# servo-hbridge.net
KiCad netlist of a schematic drawn in Altium Designer
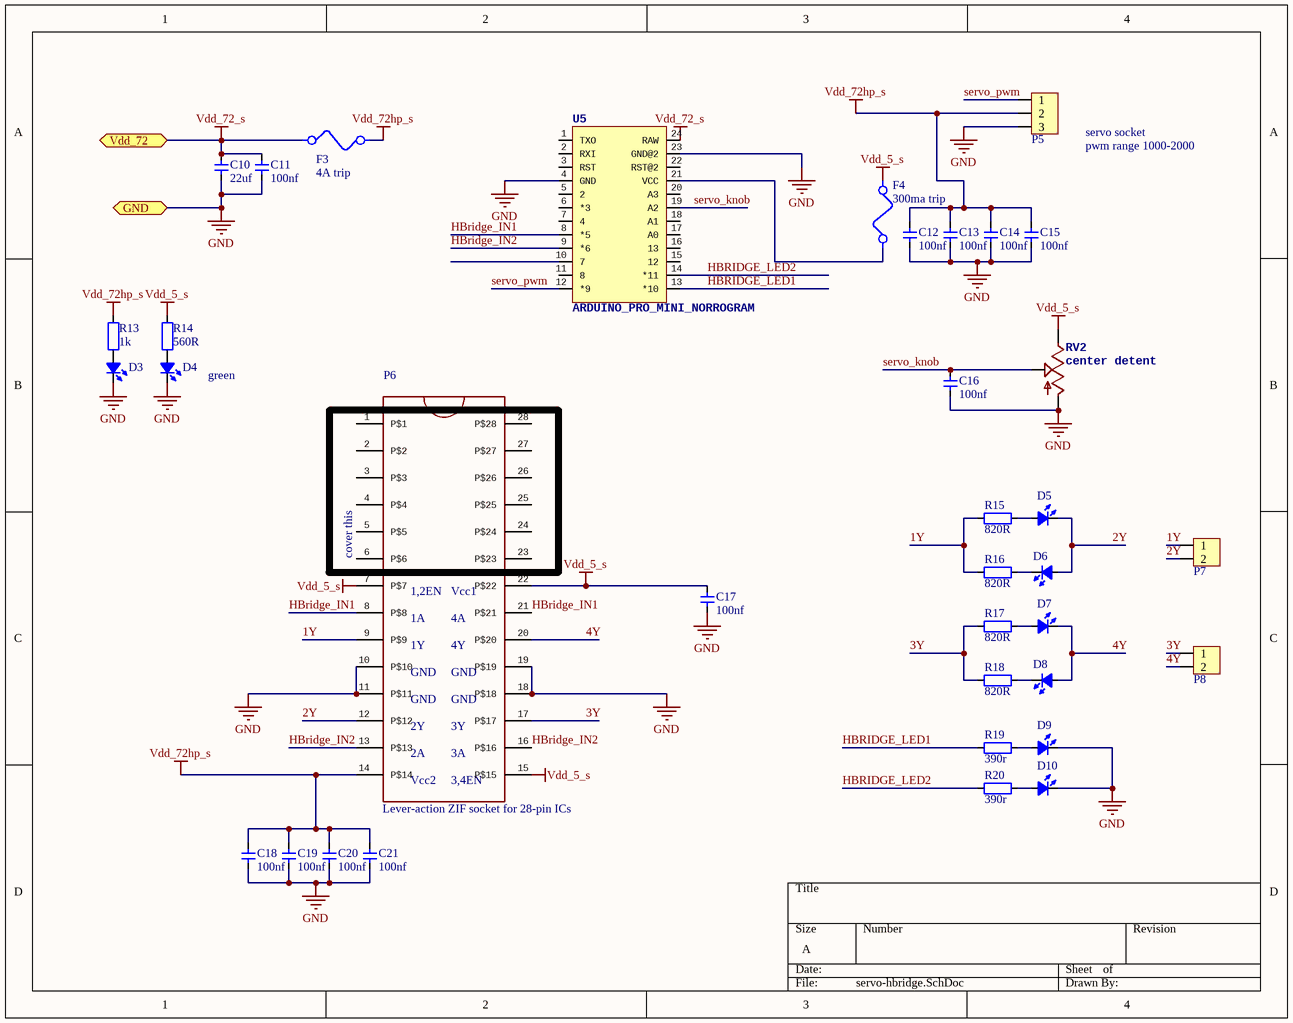
[diagram p0: servo-hbridge.SchDoc]

(export (version "E")
  (design (tool "Eeschema 10.0.6"))
  (components
    (comp (ref "C10")
      (value "22uf")
      (footprint "PCB_PassiveCap:CAP_0805")
      (description "Capacitor")
      (fields (field (name "Comment") "Cap_0805"))
      (libsource (lib "SCH_Passive") (part "Cap_0805"))
    )
    (comp (ref "C11")
      (value "100nf")
      (footprint "PCB_PassiveCap:CAP_0805")
      (description "Capacitor")
      (fields (field (name "Comment") "Cap_0805"))
      (libsource (lib "SCH_Passive") (part "Cap_0805"))
    )
    (comp (ref "C12")
      (value "100nf")
      (footprint "PCB_PassiveCap:CAP_0805")
      (description "Capacitor")
      (fields (field (name "Comment") "Cap_0805"))
      (libsource (lib "SCH_Passive") (part "Cap_0805"))
    )
    (comp (ref "C13")
      (value "100nf")
      (footprint "PCB_PassiveCap:CAP_0805")
      (description "Capacitor")
      (fields (field (name "Comment") "Cap_0805"))
      (libsource (lib "SCH_Passive") (part "Cap_0805"))
    )
    (comp (ref "C14")
      (value "100nf")
      (footprint "PCB_PassiveCap:CAP_0805")
      (description "Capacitor")
      (fields (field (name "Comment") "Cap_0805"))
      (libsource (lib "SCH_Passive") (part "Cap_0805"))
    )
    (comp (ref "C15")
      (value "100nf")
      (footprint "PCB_PassiveCap:CAP_0805")
      (description "Capacitor")
      (fields (field (name "Comment") "Cap_0805"))
      (libsource (lib "SCH_Passive") (part "Cap_0805"))
    )
    (comp (ref "C16")
      (value "100nf")
      (footprint "PCB_PassiveCap:CAP_0805")
      (description "Capacitor")
      (fields (field (name "Comment") "Cap_0805"))
      (libsource (lib "SCH_Passive") (part "Cap_0805"))
    )
    (comp (ref "C17")
      (value "100nf")
      (footprint "PCB_PassiveCap:CAP_0805")
      (description "Capacitor")
      (fields (field (name "Comment") "Cap_0805"))
      (libsource (lib "SCH_Passive") (part "Cap_0805"))
    )
    (comp (ref "C18")
      (value "100nf")
      (footprint "PCB_PassiveCap:CAP_0805")
      (description "Capacitor")
      (fields (field (name "Comment") "Cap_0805"))
      (libsource (lib "SCH_Passive") (part "Cap_0805"))
    )
    (comp (ref "C19")
      (value "100nf")
      (footprint "PCB_PassiveCap:CAP_0805")
      (description "Capacitor")
      (fields (field (name "Comment") "Cap_0805"))
      (libsource (lib "SCH_Passive") (part "Cap_0805"))
    )
    (comp (ref "C20")
      (value "100nf")
      (footprint "PCB_PassiveCap:CAP_0805")
      (description "Capacitor")
      (fields (field (name "Comment") "Cap_0805"))
      (libsource (lib "SCH_Passive") (part "Cap_0805"))
    )
    (comp (ref "C21")
      (value "100nf")
      (footprint "PCB_PassiveCap:CAP_0805")
      (description "Capacitor")
      (fields (field (name "Comment") "Cap_0805"))
      (libsource (lib "SCH_Passive") (part "Cap_0805"))
    )
    (comp (ref "D3")
      (value "LED_0805")
      (footprint "PCB_ActiveLED:LED_0805_RED")
      (description "LED")
      (libsource (lib "SCH_Active") (part "LED_0805"))
    )
    (comp (ref "D4")
      (value "LED_0805")
      (footprint "PCB_ActiveLED:LED_0805_RED")
      (description "LED")
      (libsource (lib "SCH_Active") (part "LED_0805"))
    )
    (comp (ref "D5")
      (value "LED_0805")
      (footprint "PCB_ActiveLED:LED_0805_YELLOW")
      (description "LED")
      (libsource (lib "SCH_Active") (part "LED_0805"))
    )
    (comp (ref "D6")
      (value "LED_0805")
      (footprint "PCB_ActiveLED:LED_0805_YELLOW")
      (description "LED")
      (libsource (lib "SCH_Active") (part "LED_0805"))
    )
    (comp (ref "D7")
      (value "LED_0805")
      (footprint "PCB_ActiveLED:LED_0805_YELLOW")
      (description "LED")
      (libsource (lib "SCH_Active") (part "LED_0805"))
    )
    (comp (ref "D8")
      (value "LED_0805")
      (footprint "PCB_ActiveLED:LED_0805_YELLOW")
      (description "LED")
      (libsource (lib "SCH_Active") (part "LED_0805"))
    )
    (comp (ref "D9")
      (value "LED_0805")
      (footprint "PCB_ActiveLED:LED_0805_YELLOW")
      (description "LED")
      (libsource (lib "SCH_Active") (part "LED_0805"))
    )
    (comp (ref "D10")
      (value "LED_0805")
      (footprint "PCB_ActiveLED:LED_0805_YELLOW")
      (description "LED")
      (libsource (lib "SCH_Active") (part "LED_0805"))
    )
    (comp (ref "F3")
      (value "4A trip")
      (footprint "Multifuse1812")
      (description "RO ZEK MULTI 500MA SMD 1812 MF-MSMF050-2 BOURNS")
      (fields (field (name "MFG") "BOURNS"))
      (libsource (lib "Ultimaker") (part "Multifuse"))
    )
    (comp (ref "F4")
      (value "300ma trip")
      (footprint "Multifuse1812")
      (description "RO ZEK MULTI 500MA SMD 1812 MF-MSMF050-2 BOURNS")
      (fields (field (name "MFG") "BOURNS"))
      (libsource (lib "Ultimaker") (part "Multifuse"))
    )
    (comp (ref "P5")
      (value "HDR1x3_2.54")
      (footprint "PCB_ConnectorHDR:HDR1X3_2.54_180")
      (description "Header")
      (libsource (lib "SCH_ConnectorHDR") (part "HDR1x3_2.54"))
    )
    (comp (ref "P6")
      (value "Lever-action ZIF socket for 28-pin ICs")
      (footprint "DIL28-3-ZIF_SOCKET")
      (libsource (lib "SparkFun-Connectors") (part "ZIFSOCKET-28-3ZIFFSOCKET-28-3"))
    )
    (comp (ref "P7")
      (value "HDR1x2_2.54")
      (footprint "PCB_ConnectorHDR:HDR1X2_2.54_180")
      (description "Header")
      (libsource (lib "SCH_ConnectorHDR") (part "HDR1x2_2.54"))
    )
    (comp (ref "P8")
      (value "HDR1x2_2.54")
      (footprint "PCB_ConnectorHDR:HDR1X2_2.54_180")
      (description "Header")
      (libsource (lib "SCH_ConnectorHDR") (part "HDR1x2_2.54"))
    )
    (comp (ref "R13")
      (value "1k")
      (footprint "PCB_PassiveRes:RES_0805")
      (description "Resistor")
      (fields (field (name "Comment") "Res_0805"))
      (libsource (lib "") (part "Res_0805_1"))
    )
    (comp (ref "R14")
      (value "560R")
      (footprint "PCB_PassiveRes:RES_0805")
      (description "Resistor")
      (fields (field (name "Comment") "Res_0805"))
      (libsource (lib "") (part "Res_0805_1"))
    )
    (comp (ref "R15")
      (value "820R")
      (footprint "PCB_PassiveRes:RES_0805")
      (description "Resistor")
      (fields (field (name "Comment") "Res_0805"))
      (libsource (lib "SCH_Passive") (part "Res_0805"))
    )
    (comp (ref "R16")
      (value "820R")
      (footprint "PCB_PassiveRes:RES_0805")
      (description "Resistor")
      (fields (field (name "Comment") "Res_0805"))
      (libsource (lib "SCH_Passive") (part "Res_0805"))
    )
    (comp (ref "R17")
      (value "820R")
      (footprint "PCB_PassiveRes:RES_0805")
      (description "Resistor")
      (fields (field (name "Comment") "Res_0805"))
      (libsource (lib "SCH_Passive") (part "Res_0805"))
    )
    (comp (ref "R18")
      (value "820R")
      (footprint "PCB_PassiveRes:RES_0805")
      (description "Resistor")
      (fields (field (name "Comment") "Res_0805"))
      (libsource (lib "SCH_Passive") (part "Res_0805"))
    )
    (comp (ref "R19")
      (value "390r")
      (footprint "PCB_PassiveRes:RES_0805")
      (description "Resistor")
      (fields (field (name "Comment") "Res_0805"))
      (libsource (lib "SCH_Passive") (part "Res_0805"))
    )
    (comp (ref "R20")
      (value "390r")
      (footprint "PCB_PassiveRes:RES_0805")
      (description "Resistor")
      (fields (field (name "Comment") "Res_0805"))
      (libsource (lib "SCH_Passive") (part "Res_0805"))
    )
    (comp (ref "RV2")
      (value "center detent")
      (footprint "Bourns-slimline-axialbracket")
      (libsource (lib "SparkFun-Electromechanical") (part "POTALPS-KIT"))
    )
    (comp (ref "U5")
      (value "ARDUINO_PRO_MINI_NORROGRAM")
      (footprint "ARDUINO_PRO_MINI_NOPROGRAM")
      (libsource (lib "SparkFun-Boards") (part "ARDUINO_PRO_MINI_NORROGRAM"))
    )
  )
  (nets
    (net (code "1") (name "/1Y") (class "Default")
      (node (ref "P6") (pin "9") (pinfunction "P$9_9") (pintype "passive"))
      (node (ref "P7") (pin "1") (pinfunction "1_1") (pintype "passive"))
      (node (ref "R15") (pin "1") (pinfunction "1_1") (pintype "passive"))
      (node (ref "R16") (pin "1") (pinfunction "1_1") (pintype "passive"))
    )
    (net (code "2") (name "/2Y") (class "Default")
      (node (ref "D5") (pin "2") (pinfunction "K_2") (pintype "passive"))
      (node (ref "D6") (pin "1") (pinfunction "A_1") (pintype "passive"))
      (node (ref "P6") (pin "12") (pinfunction "P$12_12") (pintype "passive"))
      (node (ref "P7") (pin "2") (pinfunction "2_2") (pintype "passive"))
    )
    (net (code "3") (name "/3Y") (class "Default")
      (node (ref "P6") (pin "17") (pinfunction "P$17_17") (pintype "passive"))
      (node (ref "P8") (pin "1") (pinfunction "1_1") (pintype "passive"))
      (node (ref "R17") (pin "1") (pinfunction "1_1") (pintype "passive"))
      (node (ref "R18") (pin "1") (pinfunction "1_1") (pintype "passive"))
    )
    (net (code "4") (name "/4Y") (class "Default")
      (node (ref "D7") (pin "2") (pinfunction "K_2") (pintype "passive"))
      (node (ref "D8") (pin "1") (pinfunction "A_1") (pintype "passive"))
      (node (ref "P6") (pin "20") (pinfunction "P$20_20") (pintype "passive"))
      (node (ref "P8") (pin "2") (pinfunction "2_2") (pintype "passive"))
    )
    (net (code "5") (name "/HBRIDGE_LED1") (class "Default")
      (node (ref "R19") (pin "1") (pinfunction "1_1") (pintype "passive"))
      (node (ref "U5") (pin "13") (pinfunction "*10_13") (pintype "passive"))
    )
    (net (code "6") (name "/HBRIDGE_LED2") (class "Default")
      (node (ref "R20") (pin "1") (pinfunction "1_1") (pintype "passive"))
      (node (ref "U5") (pin "14") (pinfunction "*11_14") (pintype "passive"))
    )
    (net (code "7") (name "/HBridge_IN1") (class "Default")
      (node (ref "P6") (pin "21") (pinfunction "P$21_21") (pintype "passive"))
      (node (ref "P6") (pin "8") (pinfunction "P$8_8") (pintype "passive"))
      (node (ref "U5") (pin "8") (pinfunction "*5_8") (pintype "passive"))
    )
    (net (code "8") (name "/HBridge_IN2") (class "Default")
      (node (ref "P6") (pin "13") (pinfunction "P$13_13") (pintype "passive"))
      (node (ref "P6") (pin "16") (pinfunction "P$16_16") (pintype "passive"))
      (node (ref "U5") (pin "9") (pinfunction "*6_9") (pintype "passive"))
    )
    (net (code "9") (name "/servo_knob") (class "Default")
      (node (ref "C16") (pin "1") (pinfunction "1_1") (pintype "passive"))
      (node (ref "RV2") (pin "P$2") (pinfunction "S_P$2") (pintype "passive"))
      (node (ref "U5") (pin "19") (pinfunction "A2_19") (pintype "passive"))
    )
    (net (code "10") (name "/servo_pwm") (class "Default")
      (node (ref "P5") (pin "1") (pinfunction "1_1") (pintype "passive"))
      (node (ref "U5") (pin "12") (pinfunction "*9_12") (pintype "passive"))
    )
    (net (code "11") (name "GND") (class "Default")
      (node (ref "C10") (pin "1") (pinfunction "1_1") (pintype "passive"))
      (node (ref "C11") (pin "1") (pinfunction "1_1") (pintype "passive"))
      (node (ref "C12") (pin "2") (pinfunction "2_2") (pintype "passive"))
      (node (ref "C13") (pin "2") (pinfunction "2_2") (pintype "passive"))
      (node (ref "C14") (pin "2") (pinfunction "2_2") (pintype "passive"))
      (node (ref "C15") (pin "2") (pinfunction "2_2") (pintype "passive"))
      (node (ref "C16") (pin "2") (pinfunction "2_2") (pintype "passive"))
      (node (ref "C17") (pin "1") (pinfunction "1_1") (pintype "passive"))
      (node (ref "C18") (pin "2") (pinfunction "2_2") (pintype "passive"))
      (node (ref "C19") (pin "2") (pinfunction "2_2") (pintype "passive"))
      (node (ref "C20") (pin "2") (pinfunction "2_2") (pintype "passive"))
      (node (ref "C21") (pin "2") (pinfunction "2_2") (pintype "passive"))
      (node (ref "D10") (pin "2") (pinfunction "K_2") (pintype "passive"))
      (node (ref "D3") (pin "2") (pinfunction "K_2") (pintype "passive"))
      (node (ref "D4") (pin "2") (pinfunction "K_2") (pintype "passive"))
      (node (ref "D9") (pin "2") (pinfunction "K_2") (pintype "passive"))
      (node (ref "P5") (pin "3") (pinfunction "3_3") (pintype "passive"))
      (node (ref "P6") (pin "10") (pinfunction "P$10_10") (pintype "passive"))
      (node (ref "P6") (pin "11") (pinfunction "P$11_11") (pintype "passive"))
      (node (ref "P6") (pin "18") (pinfunction "P$18_18") (pintype "passive"))
      (node (ref "P6") (pin "19") (pinfunction "P$19_19") (pintype "passive"))
      (node (ref "RV2") (pin "P$3") (pinfunction "A_P$3") (pintype "passive"))
      (node (ref "U5") (pin "23") (pinfunction "GND@2_23") (pintype "passive"))
      (node (ref "U5") (pin "4") (pinfunction "GND_4") (pintype "passive"))
    )
    (net (code "12") (name "Net-(D3-A)") (class "Default")
      (node (ref "D3") (pin "1") (pinfunction "A_1") (pintype "passive"))
      (node (ref "R13") (pin "1") (pinfunction "1_1") (pintype "passive"))
    )
    (net (code "13") (name "Net-(D4-A)") (class "Default")
      (node (ref "D4") (pin "1") (pinfunction "A_1") (pintype "passive"))
      (node (ref "R14") (pin "1") (pinfunction "1_1") (pintype "passive"))
    )
    (net (code "14") (name "Net-(D5-A)") (class "Default")
      (node (ref "D5") (pin "1") (pinfunction "A_1") (pintype "passive"))
      (node (ref "R15") (pin "2") (pinfunction "2_2") (pintype "passive"))
    )
    (net (code "15") (name "Net-(D6-K)") (class "Default")
      (node (ref "D6") (pin "2") (pinfunction "K_2") (pintype "passive"))
      (node (ref "R16") (pin "2") (pinfunction "2_2") (pintype "passive"))
    )
    (net (code "16") (name "Net-(D7-A)") (class "Default")
      (node (ref "D7") (pin "1") (pinfunction "A_1") (pintype "passive"))
      (node (ref "R17") (pin "2") (pinfunction "2_2") (pintype "passive"))
    )
    (net (code "17") (name "Net-(D8-K)") (class "Default")
      (node (ref "D8") (pin "2") (pinfunction "K_2") (pintype "passive"))
      (node (ref "R18") (pin "2") (pinfunction "2_2") (pintype "passive"))
    )
    (net (code "18") (name "Net-(D9-A)") (class "Default")
      (node (ref "D9") (pin "1") (pinfunction "A_1") (pintype "passive"))
      (node (ref "R19") (pin "2") (pinfunction "2_2") (pintype "passive"))
    )
    (net (code "19") (name "Net-(D10-A)") (class "Default")
      (node (ref "D10") (pin "1") (pinfunction "A_1") (pintype "passive"))
      (node (ref "R20") (pin "2") (pinfunction "2_2") (pintype "passive"))
    )
    (net (code "20") (name "Net-(U5-VCC)") (class "Default")
      (node (ref "F4") (pin "1") (pinfunction "1_1") (pintype "passive"))
      (node (ref "U5") (pin "21") (pinfunction "VCC_21") (pintype "passive"))
    )
    (net (code "21") (name "Vdd_5_s") (class "Default")
      (node (ref "C17") (pin "2") (pinfunction "2_2") (pintype "passive"))
      (node (ref "F4") (pin "2") (pinfunction "2_2") (pintype "passive"))
      (node (ref "P6") (pin "15") (pinfunction "P$15_15") (pintype "passive"))
      (node (ref "P6") (pin "22") (pinfunction "P$22_22") (pintype "passive"))
      (node (ref "P6") (pin "7") (pinfunction "P$7_7") (pintype "passive"))
      (node (ref "R14") (pin "2") (pinfunction "2_2") (pintype "passive"))
      (node (ref "RV2") (pin "P$1") (pinfunction "E_P$1") (pintype "passive"))
    )
    (net (code "22") (name "Vdd_72_s") (class "Default")
      (node (ref "C10") (pin "2") (pinfunction "2_2") (pintype "passive"))
      (node (ref "C11") (pin "2") (pinfunction "2_2") (pintype "passive"))
      (node (ref "F3") (pin "1") (pinfunction "1_1") (pintype "passive"))
      (node (ref "U5") (pin "24") (pinfunction "RAW_24") (pintype "passive"))
    )
    (net (code "23") (name "Vdd_72hp_s") (class "Default")
      (node (ref "C12") (pin "1") (pinfunction "1_1") (pintype "passive"))
      (node (ref "C13") (pin "1") (pinfunction "1_1") (pintype "passive"))
      (node (ref "C14") (pin "1") (pinfunction "1_1") (pintype "passive"))
      (node (ref "C15") (pin "1") (pinfunction "1_1") (pintype "passive"))
      (node (ref "C18") (pin "1") (pinfunction "1_1") (pintype "passive"))
      (node (ref "C19") (pin "1") (pinfunction "1_1") (pintype "passive"))
      (node (ref "C20") (pin "1") (pinfunction "1_1") (pintype "passive"))
      (node (ref "C21") (pin "1") (pinfunction "1_1") (pintype "passive"))
      (node (ref "F3") (pin "2") (pinfunction "2_2") (pintype "passive"))
      (node (ref "P5") (pin "2") (pinfunction "2_2") (pintype "passive"))
      (node (ref "P6") (pin "14") (pinfunction "P$14_14") (pintype "passive"))
      (node (ref "R13") (pin "2") (pinfunction "2_2") (pintype "passive"))
    )
    (net (code "24") (name "unconnected-(P6-P$1-Pad1)") (class "Default")
      (node (ref "P6") (pin "1") (pinfunction "P$1_1") (pintype "passive"))
    )
    (net (code "25") (name "unconnected-(P6-P$2-Pad2)") (class "Default")
      (node (ref "P6") (pin "2") (pinfunction "P$2_2") (pintype "passive"))
    )
    (net (code "26") (name "unconnected-(P6-P$3-Pad3)") (class "Default")
      (node (ref "P6") (pin "3") (pinfunction "P$3_3") (pintype "passive"))
    )
    (net (code "27") (name "unconnected-(P6-P$4-Pad4)") (class "Default")
      (node (ref "P6") (pin "4") (pinfunction "P$4_4") (pintype "passive"))
    )
    (net (code "28") (name "unconnected-(P6-P$5-Pad5)") (class "Default")
      (node (ref "P6") (pin "5") (pinfunction "P$5_5") (pintype "passive"))
    )
    (net (code "29") (name "unconnected-(P6-P$6-Pad6)") (class "Default")
      (node (ref "P6") (pin "6") (pinfunction "P$6_6") (pintype "passive"))
    )
    (net (code "30") (name "unconnected-(P6-P$23-Pad23)") (class "Default")
      (node (ref "P6") (pin "23") (pinfunction "P$23_23") (pintype "passive"))
    )
    (net (code "31") (name "unconnected-(P6-P$24-Pad24)") (class "Default")
      (node (ref "P6") (pin "24") (pinfunction "P$24_24") (pintype "passive"))
    )
    (net (code "32") (name "unconnected-(P6-P$25-Pad25)") (class "Default")
      (node (ref "P6") (pin "25") (pinfunction "P$25_25") (pintype "passive"))
    )
    (net (code "33") (name "unconnected-(P6-P$26-Pad26)") (class "Default")
      (node (ref "P6") (pin "26") (pinfunction "P$26_26") (pintype "passive"))
    )
    (net (code "34") (name "unconnected-(P6-P$27-Pad27)") (class "Default")
      (node (ref "P6") (pin "27") (pinfunction "P$27_27") (pintype "passive"))
    )
    (net (code "35") (name "unconnected-(P6-P$28-Pad28)") (class "Default")
      (node (ref "P6") (pin "28") (pinfunction "P$28_28") (pintype "passive"))
    )
    (net (code "36") (name "unconnected-(U5-*3-Pad6)") (class "Default")
      (node (ref "U5") (pin "6") (pinfunction "*3_6") (pintype "passive"))
    )
    (net (code "37") (name "unconnected-(U5-2-Pad5)") (class "Default")
      (node (ref "U5") (pin "5") (pinfunction "2_5") (pintype "passive"))
    )
    (net (code "38") (name "unconnected-(U5-4-Pad7)") (class "Default")
      (node (ref "U5") (pin "7") (pinfunction "4_7") (pintype "passive"))
    )
    (net (code "39") (name "unconnected-(U5-7-Pad10)") (class "Default")
      (node (ref "U5") (pin "10") (pinfunction "7_10") (pintype "passive"))
    )
    (net (code "40") (name "unconnected-(U5-8-Pad11)") (class "Default")
      (node (ref "U5") (pin "11") (pinfunction "8_11") (pintype "passive"))
    )
    (net (code "41") (name "unconnected-(U5-12-Pad15)") (class "Default")
      (node (ref "U5") (pin "15") (pinfunction "12_15") (pintype "passive"))
    )
    (net (code "42") (name "unconnected-(U5-13-Pad16)") (class "Default")
      (node (ref "U5") (pin "16") (pinfunction "13_16") (pintype "passive"))
    )
    (net (code "43") (name "unconnected-(U5-A0-Pad17)") (class "Default")
      (node (ref "U5") (pin "17") (pinfunction "A0_17") (pintype "passive"))
    )
    (net (code "44") (name "unconnected-(U5-A1-Pad18)") (class "Default")
      (node (ref "U5") (pin "18") (pinfunction "A1_18") (pintype "passive"))
    )
    (net (code "45") (name "unconnected-(U5-A3-Pad20)") (class "Default")
      (node (ref "U5") (pin "20") (pinfunction "A3_20") (pintype "passive"))
    )
    (net (code "46") (name "unconnected-(U5-RST-Pad3)") (class "Default")
      (node (ref "U5") (pin "3") (pinfunction "RST_3") (pintype "passive"))
    )
    (net (code "47") (name "unconnected-(U5-RST@2-Pad22)") (class "Default")
      (node (ref "U5") (pin "22") (pinfunction "RST@2_22") (pintype "passive"))
    )
    (net (code "48") (name "unconnected-(U5-RXI-Pad2)") (class "Default")
      (node (ref "U5") (pin "2") (pinfunction "RXI_2") (pintype "passive"))
    )
    (net (code "49") (name "unconnected-(U5-TXO-Pad1)") (class "Default")
      (node (ref "U5") (pin "1") (pinfunction "TXO_1") (pintype "passive"))
    )
  )
)
